# STM32F1xx.net
KiCad netlist of a schematic drawn in Altium Designer
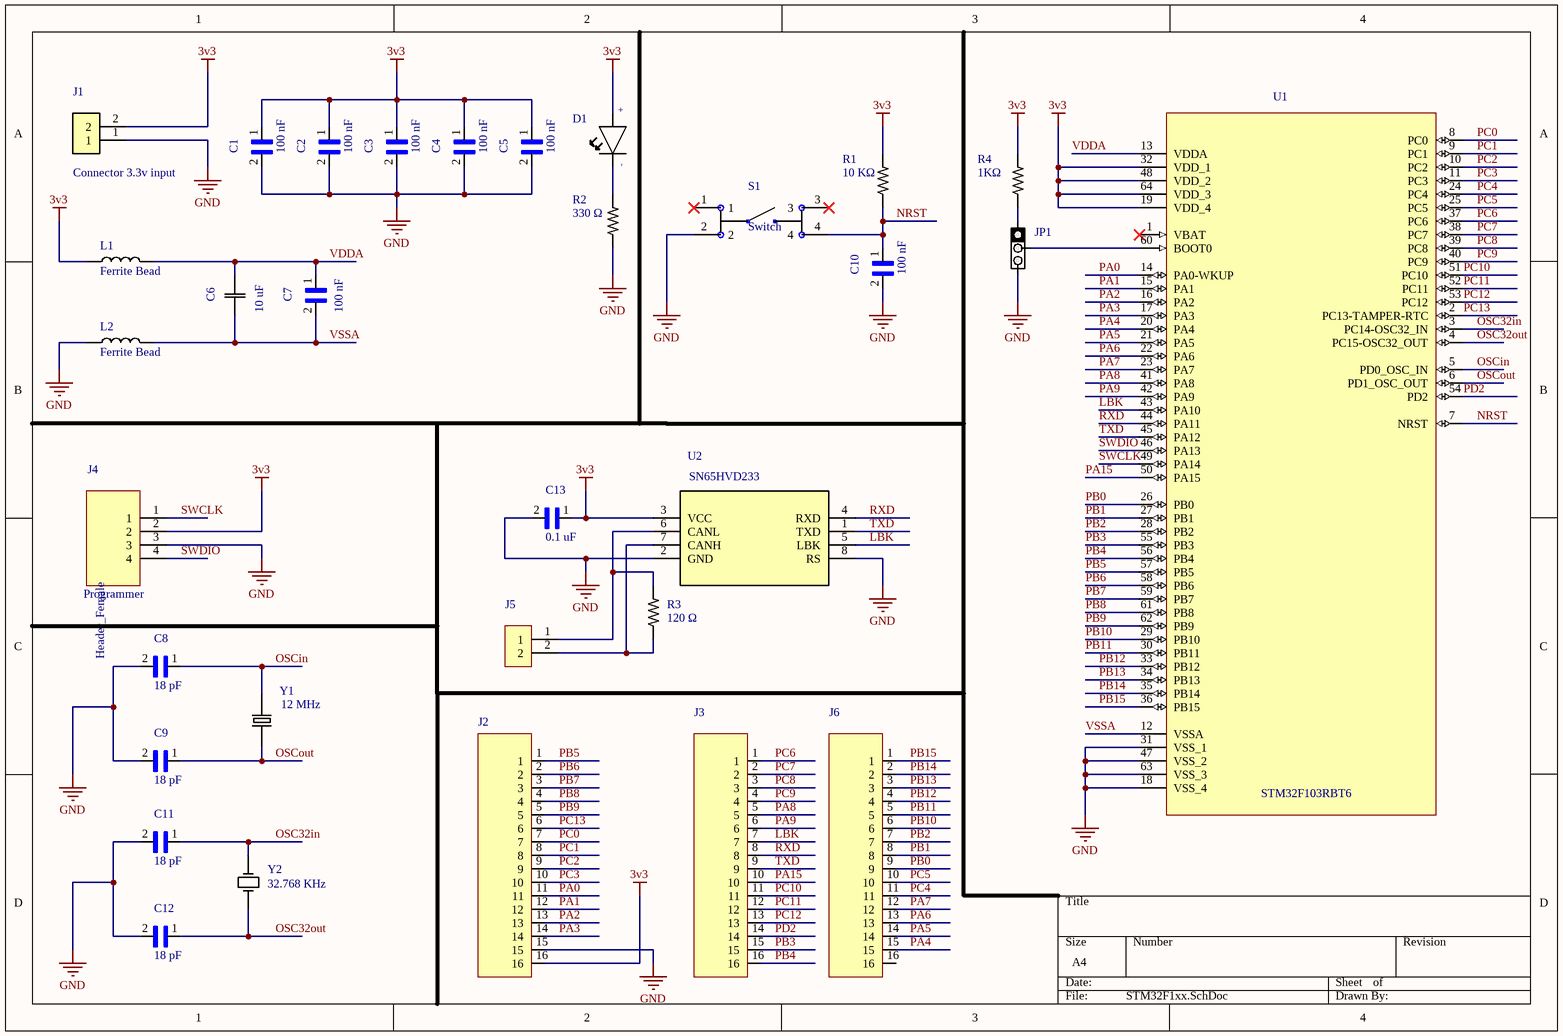
[diagram p0: STM32F1xx.SchDoc]

(export (version "E")
  (design (tool "Eeschema 10.0.6"))
  (components
    (comp (ref "C1")
      (value "100 nF")
      (footprint "*CAPC2012X135N")
      (description "Cap Ceramic 0.1uF 50Vdc X7R 10% SMD 805 125Â°C Embossed T/R")
      (fields (field (name "MF") "Murata Electronics") (field (name "MP") "GCD21BR71H104KA01L"))
      (libsource (lib "Cap_805") (part "GCD21BR71H104KA01L"))
    )
    (comp (ref "C2")
      (value "100 nF")
      (footprint "*CAPC2012X135N")
      (description "Cap Ceramic 0.1uF 50Vdc X7R 10% SMD 805 125Â°C Embossed T/R")
      (fields (field (name "MF") "Murata Electronics") (field (name "MP") "GCD21BR71H104KA01L"))
      (libsource (lib "Cap_805") (part "GCD21BR71H104KA01L"))
    )
    (comp (ref "C3")
      (value "100 nF")
      (footprint "*CAPC2012X135N")
      (description "Cap Ceramic 0.1uF 50Vdc X7R 10% SMD 805 125Â°C Embossed T/R")
      (fields (field (name "MF") "Murata Electronics") (field (name "MP") "GCD21BR71H104KA01L"))
      (libsource (lib "Cap_805") (part "GCD21BR71H104KA01L"))
    )
    (comp (ref "C4")
      (value "100 nF")
      (footprint "*CAPC2012X135N")
      (description "Cap Ceramic 0.1uF 50Vdc X7R 10% SMD 805 125Â°C Embossed T/R")
      (fields (field (name "MF") "Murata Electronics") (field (name "MP") "GCD21BR71H104KA01L"))
      (libsource (lib "Cap_805") (part "GCD21BR71H104KA01L"))
    )
    (comp (ref "C5")
      (value "100 nF")
      (footprint "*CAPC2012X135N")
      (description "Cap Ceramic 0.1uF 50Vdc X7R 10% SMD 805 125Â°C Embossed T/R")
      (fields (field (name "MF") "Murata Electronics") (field (name "MP") "GCD21BR71H104KA01L"))
      (libsource (lib "Cap_805") (part "GCD21BR71H104KA01L"))
    )
    (comp (ref "C6")
      (value "10 uF")
      (footprint "CAPC3216X94N")
      (description "1206 100 nF 16 V Â±10 % Tolerance X7R SMT Multilayer Ceramic Capacitor")
      (fields (field (name "MP") "1206YC104KAT2A") (field (name "MF") "AVX"))
      (libsource (lib "Cap_1206") (part "1206YC104KAT2A"))
    )
    (comp (ref "C7")
      (value "100 nF")
      (footprint "*CAPC2012X135N")
      (description "Cap Ceramic 0.1uF 50Vdc X7R 10% SMD 805 125Â°C Embossed T/R")
      (fields (field (name "MF") "Murata Electronics") (field (name "MP") "GCD21BR71H104KA01L"))
      (libsource (lib "Cap_805") (part "GCD21BR71H104KA01L"))
    )
    (comp (ref "C8")
      (value "18 pF")
      (footprint "*CAPC2012X135N")
      (description "Cap Ceramic 0.1uF 50Vdc X7R 10% SMD 805 125Â°C Embossed T/R")
      (fields (field (name "MF") "Murata Electronics") (field (name "MP") "GCD21BR71H104KA01L"))
      (libsource (lib "Cap_805") (part "GCD21BR71H104KA01L"))
    )
    (comp (ref "C9")
      (value "18 pF")
      (footprint "*CAPC2012X135N")
      (description "Cap Ceramic 0.1uF 50Vdc X7R 10% SMD 805 125Â°C Embossed T/R")
      (fields (field (name "MF") "Murata Electronics") (field (name "MP") "GCD21BR71H104KA01L"))
      (libsource (lib "Cap_805") (part "GCD21BR71H104KA01L"))
    )
    (comp (ref "C10")
      (value "100 nF")
      (footprint "*CAPC2012X135N")
      (description "Cap Ceramic 0.1uF 50Vdc X7R 10% SMD 805 125Â°C Embossed T/R")
      (fields (field (name "MF") "Murata Electronics") (field (name "MP") "GCD21BR71H104KA01L"))
      (libsource (lib "Cap_805") (part "GCD21BR71H104KA01L"))
    )
    (comp (ref "C11")
      (value "18 pF")
      (footprint "*CAPC2012X135N")
      (description "Cap Ceramic 0.1uF 50Vdc X7R 10% SMD 805 125Â°C Embossed T/R")
      (fields (field (name "MF") "Murata Electronics") (field (name "MP") "GCD21BR71H104KA01L"))
      (libsource (lib "Cap_805") (part "GCD21BR71H104KA01L"))
    )
    (comp (ref "C12")
      (value "18 pF")
      (footprint "*CAPC2012X135N")
      (description "Cap Ceramic 0.1uF 50Vdc X7R 10% SMD 805 125Â°C Embossed T/R")
      (fields (field (name "MF") "Murata Electronics") (field (name "MP") "GCD21BR71H104KA01L"))
      (libsource (lib "Cap_805") (part "GCD21BR71H104KA01L"))
    )
    (comp (ref "C13")
      (value "0.1 uF")
      (footprint "*CAPC2012X135N")
      (description "Cap Ceramic 0.1uF 50Vdc X7R 10% SMD 805 125Â°C Embossed T/R")
      (fields (field (name "MF") "Murata Electronics") (field (name "MP") "GCD21BR71H104KA01L"))
      (libsource (lib "Cap_805") (part "GCD21BR71H104KA01L"))
    )
    (comp (ref "D1")
      (value "LED1206")
      (footprint "WL-SMCW_0603")
      (description "LED, 1206, AMBER, 140MCD, 605NM; Bulb Size: -; LED Colour: Ambre; Luminous Intensi")
      (fields (field (name "MF") "Wurth Electronics") (field (name "DIGI-KEY_PART_NUMBER") "732-4988-1-ND"))
      (libsource (lib "LED_0805") (part "WL-SMCW"))
    )
    (comp (ref "J1")
      (value "Connector 3.3v input")
      (footprint "*MOLEX_0022272031")
      (fields
        (field (name "DIGI-KEY_PART_NUMBER") "WM4112-ND")
        (field (name "MF") "Molex")
        (field (name "MP") "0022272031")
      )
      (libsource (lib "Connector_2Pins") (part "0022272031"))
    )
    (comp (ref "J2")
      (value "Pin Header")
      (footprint "*TE_9-146281-0")
      (description "20 MODII HDR SRST")
      (fields (field (name "CREATED BY") "Alireza Nami"))
      (libsource (lib "Header_F_16") (part "Pin Header"))
    )
    (comp (ref "J3")
      (value "Pin Header")
      (footprint "*TE_9-146281-0")
      (description "20 MODII HDR SRST")
      (fields (field (name "CREATED BY") "Alireza Nami"))
      (libsource (lib "Header_F_16") (part "Pin Header"))
    )
    (comp (ref "J4")
      (value "Programmer")
      (footprint "TE_7-534206-0")
      (description "40 MODII VRT DR CE 100/115")
      (fields (field (name "MP") "7-534206-0") (field (name "MF") "TE Connectivity"))
      (libsource (lib "Header_F_4") (part "7-534206-0"))
    )
    (comp (ref "J5")
      (value "Terminal")
      (footprint "TE_1776266-4")
      (description "Conn Terminal Block 2 POS 5mm Screw")
      (fields (field (name "MP") "1776266-4") (field (name "MF") "TE Connectivity"))
      (libsource (lib "Terminal_2P") (part "Terminal"))
    )
    (comp (ref "J6")
      (value "Pin Header")
      (footprint "*TE_9-146281-0")
      (description "20 MODII HDR SRST")
      (fields (field (name "CREATED BY") "Alireza Nami"))
      (libsource (lib "Header_F_16") (part "Pin Header"))
    )
    (comp (ref "JP1")
      (value "JMPR3")
      (footprint "JMPR3")
      (fields
        (field (name "MANUFACTURER") "Sullins Connector Solutions")
        (field (name "MANUFACTURER PART NUMBER") "PBC36SAAN")
      )
      (libsource (lib "vh_altium_library") (part "JMPR3"))
    )
    (comp (ref "L1")
      (value "Ferrite Bead")
      (footprint "*RESC3216X70")
      (fields (field (name "MF") "Panasonic") (field (name "MP") "EXCML32A680U"))
      (libsource (lib "Ferrite_Bead_1206") (part "Ferrite Bead"))
    )
    (comp (ref "L2")
      (value "Ferrite Bead")
      (footprint "*RESC3216X70")
      (fields (field (name "MF") "Panasonic") (field (name "MP") "EXCML32A680U"))
      (libsource (lib "Ferrite_Bead_1206") (part "Ferrite Bead"))
    )
    (comp (ref "R1")
      (value "10 KΩ")
      (footprint "*RESC2012X65N")
      (description "Res Thick Film 0805 118 Ohm 1% 1/3W Â±100ppm/Â°C Molded SMD SMD T/R")
      (fields (field (name "MP") "CRGH0805F118R") (field (name "MF") "TE Connectivity"))
      (libsource (lib "Res_805") (part "CRGH0805F118R"))
    )
    (comp (ref "R2")
      (value "330 Ω")
      (footprint "*RESC2012X65N")
      (description "Res Thick Film 0805 118 Ohm 1% 1/3W Â±100ppm/Â°C Molded SMD SMD T/R")
      (fields (field (name "MP") "CRGH0805F118R") (field (name "MF") "TE Connectivity"))
      (libsource (lib "Res_805") (part "CRGH0805F118R"))
    )
    (comp (ref "R3")
      (value "120 Ω")
      (footprint "*RESC2012X65N")
      (description "Res Thick Film 0805 118 Ohm 1% 1/3W Â±100ppm/Â°C Molded SMD SMD T/R")
      (fields (field (name "MP") "CRGH0805F118R") (field (name "MF") "TE Connectivity"))
      (libsource (lib "Res_805") (part "CRGH0805F118R"))
    )
    (comp (ref "R4")
      (value "1KΩ")
      (footprint "*RESC2012X65N")
      (description "Res Thick Film 0805 118 Ohm 1% 1/3W Â±100ppm/Â°C Molded SMD SMD T/R")
      (fields (field (name "MP") "CRGH0805F118R") (field (name "MF") "TE Connectivity"))
      (libsource (lib "Res_805") (part "CRGH0805F118R"))
    )
    (comp (ref "S1")
      (value "Switch")
      (footprint "SW_FSM4JSMAATR")
      (description "spst, Tactile / Jog, Industrial Control, Switches, switch, white, smd, tactile")
      (fields (field (name "MF") "Alco") (field (name "MP") "FSM4JSMAATR"))
      (libsource (lib "TactileSwitch_SMD") (part "FSM4JSMAATR"))
    )
    (comp (ref "U1")
      (value "STM32F103RBT6")
      (footprint "QFP50P1200X1200X160-64N")
      (fields (field (name "DIGI-KEY_PART_NUMBER") "497-6066-ND") (field (name "MF") "STMicroelectronics"))
      (libsource (lib "STM32F103RBT6") (part "STM32F103RBT6"))
    )
    (comp (ref "U2")
      (value "SN65HVD233")
      (footprint "*SOIC8")
      (description "Enhanced Product 3.3-V CAN Tranceiver 8-SOIC -55 to 125")
      (fields (field (name "MP") "SN65HVD233MDREP") (field (name "DIGI-KEY_PART_NUMBER") "296-23973-1-ND"))
      (libsource (lib "SN65HVD233") (part "SN65HVD233MDREP"))
    )
    (comp (ref "Y1")
      (value "12 MHz")
      (footprint "XTAL_ECS-80-18-4X")
      (description "HC-49USX Series 8 MHz Â±30 ppm 18 pF -10 to +70 Â°C Through Hole Crystal - HC-49/U")
      (fields (field (name "MP") "ECS-80-18-4X") (field (name "DIGI-KEY_PART_NUMBER") "X1093-ND"))
      (libsource (lib "Crystal_DIP") (part "ECS-80-18-4X"))
    )
    (comp (ref "Y2")
      (value "32.768 KHz")
      (footprint "*XTAL_AB38T-32.768KHZ")
      (description "AB38T Series 32.768 kHz Â±20 ppm 12.5 pF -10 to +60 Â°C Tuning Fork Crystal")
      (fields (field (name "MP") "AB38T-32.768KHZ") (field (name "MF") "Abracon"))
      (libsource (lib "Crystal_32KHz_DIP") (part "AB38T-32.768KHZ"))
    )
  )
  (nets
    (net (code "1") (name "/LBK") (class "Default")
      (node (ref "J3") (pin "7") (pinfunction "7_7") (pintype "passive"))
      (node (ref "U1") (pin "43") (pinfunction "PA10_43") (pintype "bidirectional"))
      (node (ref "U2") (pin "5") (pinfunction "LBK_5") (pintype "passive"))
    )
    (net (code "2") (name "/NRST") (class "Default")
      (node (ref "C10") (pin "1") (pinfunction "1_1") (pintype "passive"))
      (node (ref "R1") (pin "1") (pinfunction "1_1") (pintype "passive"))
      (node (ref "S1") (pin "4") (pinfunction "4_4") (pintype "passive"))
      (node (ref "U1") (pin "7") (pinfunction "NRST_7") (pintype "bidirectional"))
    )
    (net (code "3") (name "/OSC32in") (class "Default")
      (node (ref "C11") (pin "1") (pinfunction "1_1") (pintype "passive"))
      (node (ref "U1") (pin "3") (pinfunction "PC14-OSC32_IN_3") (pintype "bidirectional"))
      (node (ref "Y2") (pin "1") (pinfunction "1_1") (pintype "passive"))
    )
    (net (code "4") (name "/OSC32out") (class "Default")
      (node (ref "C12") (pin "1") (pinfunction "1_1") (pintype "passive"))
      (node (ref "U1") (pin "4") (pinfunction "PC15-OSC32_OUT_4") (pintype "bidirectional"))
      (node (ref "Y2") (pin "2") (pinfunction "2_2") (pintype "passive"))
    )
    (net (code "5") (name "/OSCin") (class "Default")
      (node (ref "C8") (pin "1") (pinfunction "1_1") (pintype "passive"))
      (node (ref "U1") (pin "5") (pinfunction "PD0_OSC_IN_5") (pintype "bidirectional"))
      (node (ref "Y1") (pin "1") (pinfunction "1_1") (pintype "passive"))
    )
    (net (code "6") (name "/OSCout") (class "Default")
      (node (ref "C9") (pin "1") (pinfunction "1_1") (pintype "passive"))
      (node (ref "U1") (pin "6") (pinfunction "PD1_OSC_OUT_6") (pintype "bidirectional"))
      (node (ref "Y1") (pin "2") (pinfunction "2_2") (pintype "passive"))
    )
    (net (code "7") (name "/PA0") (class "Default")
      (node (ref "J2") (pin "11") (pinfunction "11_11") (pintype "passive"))
      (node (ref "U1") (pin "14") (pinfunction "PA0-WKUP_14") (pintype "bidirectional"))
    )
    (net (code "8") (name "/PA1") (class "Default")
      (node (ref "J2") (pin "12") (pinfunction "12_12") (pintype "passive"))
      (node (ref "U1") (pin "15") (pinfunction "PA1_15") (pintype "bidirectional"))
    )
    (net (code "9") (name "/PA2") (class "Default")
      (node (ref "J2") (pin "13") (pinfunction "13_13") (pintype "passive"))
      (node (ref "U1") (pin "16") (pinfunction "PA2_16") (pintype "bidirectional"))
    )
    (net (code "10") (name "/PA3") (class "Default")
      (node (ref "J2") (pin "14") (pinfunction "14_14") (pintype "passive"))
      (node (ref "U1") (pin "17") (pinfunction "PA3_17") (pintype "bidirectional"))
    )
    (net (code "11") (name "/PA4") (class "Default")
      (node (ref "J6") (pin "15") (pinfunction "15_15") (pintype "passive"))
      (node (ref "U1") (pin "20") (pinfunction "PA4_20") (pintype "bidirectional"))
    )
    (net (code "12") (name "/PA5") (class "Default")
      (node (ref "J6") (pin "14") (pinfunction "14_14") (pintype "passive"))
      (node (ref "U1") (pin "21") (pinfunction "PA5_21") (pintype "bidirectional"))
    )
    (net (code "13") (name "/PA6") (class "Default")
      (node (ref "J6") (pin "13") (pinfunction "13_13") (pintype "passive"))
      (node (ref "U1") (pin "22") (pinfunction "PA6_22") (pintype "bidirectional"))
    )
    (net (code "14") (name "/PA7") (class "Default")
      (node (ref "J6") (pin "12") (pinfunction "12_12") (pintype "passive"))
      (node (ref "U1") (pin "23") (pinfunction "PA7_23") (pintype "bidirectional"))
    )
    (net (code "15") (name "/PA8") (class "Default")
      (node (ref "J3") (pin "5") (pinfunction "5_5") (pintype "passive"))
      (node (ref "U1") (pin "41") (pinfunction "PA8_41") (pintype "bidirectional"))
    )
    (net (code "16") (name "/PA9") (class "Default")
      (node (ref "J3") (pin "6") (pinfunction "6_6") (pintype "passive"))
      (node (ref "U1") (pin "42") (pinfunction "PA9_42") (pintype "bidirectional"))
    )
    (net (code "17") (name "/PA15") (class "Default")
      (node (ref "J3") (pin "10") (pinfunction "10_10") (pintype "passive"))
      (node (ref "U1") (pin "50") (pinfunction "PA15_50") (pintype "bidirectional"))
    )
    (net (code "18") (name "/PB0") (class "Default")
      (node (ref "J6") (pin "9") (pinfunction "9_9") (pintype "passive"))
      (node (ref "U1") (pin "26") (pinfunction "PB0_26") (pintype "bidirectional"))
    )
    (net (code "19") (name "/PB1") (class "Default")
      (node (ref "J6") (pin "8") (pinfunction "8_8") (pintype "passive"))
      (node (ref "U1") (pin "27") (pinfunction "PB1_27") (pintype "bidirectional"))
    )
    (net (code "20") (name "/PB2") (class "Default")
      (node (ref "J6") (pin "7") (pinfunction "7_7") (pintype "passive"))
      (node (ref "U1") (pin "28") (pinfunction "PB2_28") (pintype "bidirectional"))
    )
    (net (code "21") (name "/PB3") (class "Default")
      (node (ref "J3") (pin "15") (pinfunction "15_15") (pintype "passive"))
      (node (ref "U1") (pin "55") (pinfunction "PB3_55") (pintype "bidirectional"))
    )
    (net (code "22") (name "/PB4") (class "Default")
      (node (ref "J3") (pin "16") (pinfunction "16_16") (pintype "passive"))
      (node (ref "U1") (pin "56") (pinfunction "PB4_56") (pintype "bidirectional"))
    )
    (net (code "23") (name "/PB5") (class "Default")
      (node (ref "J2") (pin "1") (pinfunction "1_1") (pintype "passive"))
      (node (ref "U1") (pin "57") (pinfunction "PB5_57") (pintype "bidirectional"))
    )
    (net (code "24") (name "/PB6") (class "Default")
      (node (ref "J2") (pin "2") (pinfunction "2_2") (pintype "passive"))
      (node (ref "U1") (pin "58") (pinfunction "PB6_58") (pintype "bidirectional"))
    )
    (net (code "25") (name "/PB7") (class "Default")
      (node (ref "J2") (pin "3") (pinfunction "3_3") (pintype "passive"))
      (node (ref "U1") (pin "59") (pinfunction "PB7_59") (pintype "bidirectional"))
    )
    (net (code "26") (name "/PB8") (class "Default")
      (node (ref "J2") (pin "4") (pinfunction "4_4") (pintype "passive"))
      (node (ref "U1") (pin "61") (pinfunction "PB8_61") (pintype "bidirectional"))
    )
    (net (code "27") (name "/PB9") (class "Default")
      (node (ref "J2") (pin "5") (pinfunction "5_5") (pintype "passive"))
      (node (ref "U1") (pin "62") (pinfunction "PB9_62") (pintype "bidirectional"))
    )
    (net (code "28") (name "/PB10") (class "Default")
      (node (ref "J6") (pin "6") (pinfunction "6_6") (pintype "passive"))
      (node (ref "U1") (pin "29") (pinfunction "PB10_29") (pintype "bidirectional"))
    )
    (net (code "29") (name "/PB11") (class "Default")
      (node (ref "J6") (pin "5") (pinfunction "5_5") (pintype "passive"))
      (node (ref "U1") (pin "30") (pinfunction "PB11_30") (pintype "bidirectional"))
    )
    (net (code "30") (name "/PB12") (class "Default")
      (node (ref "J6") (pin "4") (pinfunction "4_4") (pintype "passive"))
      (node (ref "U1") (pin "33") (pinfunction "PB12_33") (pintype "bidirectional"))
    )
    (net (code "31") (name "/PB13") (class "Default")
      (node (ref "J6") (pin "3") (pinfunction "3_3") (pintype "passive"))
      (node (ref "U1") (pin "34") (pinfunction "PB13_34") (pintype "bidirectional"))
    )
    (net (code "32") (name "/PB14") (class "Default")
      (node (ref "J6") (pin "2") (pinfunction "2_2") (pintype "passive"))
      (node (ref "U1") (pin "35") (pinfunction "PB14_35") (pintype "bidirectional"))
    )
    (net (code "33") (name "/PB15") (class "Default")
      (node (ref "J6") (pin "1") (pinfunction "1_1") (pintype "passive"))
      (node (ref "U1") (pin "36") (pinfunction "PB15_36") (pintype "bidirectional"))
    )
    (net (code "34") (name "/PC0") (class "Default")
      (node (ref "J2") (pin "7") (pinfunction "7_7") (pintype "passive"))
      (node (ref "U1") (pin "8") (pinfunction "PC0_8") (pintype "bidirectional"))
    )
    (net (code "35") (name "/PC1") (class "Default")
      (node (ref "J2") (pin "8") (pinfunction "8_8") (pintype "passive"))
      (node (ref "U1") (pin "9") (pinfunction "PC1_9") (pintype "bidirectional"))
    )
    (net (code "36") (name "/PC2") (class "Default")
      (node (ref "J2") (pin "9") (pinfunction "9_9") (pintype "passive"))
      (node (ref "U1") (pin "10") (pinfunction "PC2_10") (pintype "bidirectional"))
    )
    (net (code "37") (name "/PC3") (class "Default")
      (node (ref "J2") (pin "10") (pinfunction "10_10") (pintype "passive"))
      (node (ref "U1") (pin "11") (pinfunction "PC3_11") (pintype "bidirectional"))
    )
    (net (code "38") (name "/PC4") (class "Default")
      (node (ref "J6") (pin "11") (pinfunction "11_11") (pintype "passive"))
      (node (ref "U1") (pin "24") (pinfunction "PC4_24") (pintype "bidirectional"))
    )
    (net (code "39") (name "/PC5") (class "Default")
      (node (ref "J6") (pin "10") (pinfunction "10_10") (pintype "passive"))
      (node (ref "U1") (pin "25") (pinfunction "PC5_25") (pintype "bidirectional"))
    )
    (net (code "40") (name "/PC6") (class "Default")
      (node (ref "J3") (pin "1") (pinfunction "1_1") (pintype "passive"))
      (node (ref "U1") (pin "37") (pinfunction "PC6_37") (pintype "bidirectional"))
    )
    (net (code "41") (name "/PC7") (class "Default")
      (node (ref "J3") (pin "2") (pinfunction "2_2") (pintype "passive"))
      (node (ref "U1") (pin "38") (pinfunction "PC7_38") (pintype "bidirectional"))
    )
    (net (code "42") (name "/PC8") (class "Default")
      (node (ref "J3") (pin "3") (pinfunction "3_3") (pintype "passive"))
      (node (ref "U1") (pin "39") (pinfunction "PC8_39") (pintype "bidirectional"))
    )
    (net (code "43") (name "/PC9") (class "Default")
      (node (ref "J3") (pin "4") (pinfunction "4_4") (pintype "passive"))
      (node (ref "U1") (pin "40") (pinfunction "PC9_40") (pintype "bidirectional"))
    )
    (net (code "44") (name "/PC10") (class "Default")
      (node (ref "J3") (pin "11") (pinfunction "11_11") (pintype "passive"))
      (node (ref "U1") (pin "51") (pinfunction "PC10_51") (pintype "bidirectional"))
    )
    (net (code "45") (name "/PC11") (class "Default")
      (node (ref "J3") (pin "12") (pinfunction "12_12") (pintype "passive"))
      (node (ref "U1") (pin "52") (pinfunction "PC11_52") (pintype "bidirectional"))
    )
    (net (code "46") (name "/PC12") (class "Default")
      (node (ref "J3") (pin "13") (pinfunction "13_13") (pintype "passive"))
      (node (ref "U1") (pin "53") (pinfunction "PC12_53") (pintype "bidirectional"))
    )
    (net (code "47") (name "/PC13") (class "Default")
      (node (ref "J2") (pin "6") (pinfunction "6_6") (pintype "passive"))
      (node (ref "U1") (pin "2") (pinfunction "PC13-TAMPER-RTC_2") (pintype "bidirectional"))
    )
    (net (code "48") (name "/PD2") (class "Default")
      (node (ref "J3") (pin "14") (pinfunction "14_14") (pintype "passive"))
      (node (ref "U1") (pin "54") (pinfunction "PD2_54") (pintype "bidirectional"))
    )
    (net (code "49") (name "/RXD") (class "Default")
      (node (ref "J3") (pin "8") (pinfunction "8_8") (pintype "passive"))
      (node (ref "U1") (pin "44") (pinfunction "PA11_44") (pintype "bidirectional"))
      (node (ref "U2") (pin "4") (pinfunction "RXD_4") (pintype "passive"))
    )
    (net (code "50") (name "/SWCLK") (class "Default")
      (node (ref "J4") (pin "1") (pinfunction "1_1") (pintype "passive"))
      (node (ref "U1") (pin "49") (pinfunction "PA14_49") (pintype "bidirectional"))
    )
    (net (code "51") (name "/SWDIO") (class "Default")
      (node (ref "J4") (pin "4") (pinfunction "4_4") (pintype "passive"))
      (node (ref "U1") (pin "46") (pinfunction "PA13_46") (pintype "bidirectional"))
    )
    (net (code "52") (name "/TXD") (class "Default")
      (node (ref "J3") (pin "9") (pinfunction "9_9") (pintype "passive"))
      (node (ref "U1") (pin "45") (pinfunction "PA12_45") (pintype "bidirectional"))
      (node (ref "U2") (pin "1") (pinfunction "TXD_1") (pintype "passive"))
    )
    (net (code "53") (name "/VDDA") (class "Default")
      (node (ref "C6") (pin "2") (pinfunction "C2_2") (pintype "passive"))
      (node (ref "C7") (pin "1") (pinfunction "1_1") (pintype "passive"))
      (node (ref "L1") (pin "2") (pinfunction "2_2") (pintype "passive"))
      (node (ref "U1") (pin "13") (pinfunction "VDDA_13") (pintype "power_in"))
    )
    (net (code "54") (name "/VSSA") (class "Default")
      (node (ref "C6") (pin "1") (pinfunction "C1_1") (pintype "passive"))
      (node (ref "C7") (pin "2") (pinfunction "2_2") (pintype "passive"))
      (node (ref "L2") (pin "2") (pinfunction "2_2") (pintype "passive"))
      (node (ref "U1") (pin "12") (pinfunction "VSSA_12") (pintype "passive"))
    )
    (net (code "55") (name "3v3") (class "Default")
      (node (ref "C1") (pin "1") (pinfunction "1_1") (pintype "passive"))
      (node (ref "C13") (pin "1") (pinfunction "1_1") (pintype "passive"))
      (node (ref "C2") (pin "1") (pinfunction "1_1") (pintype "passive"))
      (node (ref "C3") (pin "1") (pinfunction "1_1") (pintype "passive"))
      (node (ref "C4") (pin "1") (pinfunction "1_1") (pintype "passive"))
      (node (ref "C5") (pin "1") (pinfunction "1_1") (pintype "passive"))
      (node (ref "D1") (pin "2") (pinfunction "2_2") (pintype "passive"))
      (node (ref "J1") (pin "2") (pinfunction "2_2") (pintype "passive"))
      (node (ref "J2") (pin "16") (pinfunction "16_16") (pintype "passive"))
      (node (ref "J4") (pin "2") (pinfunction "2_2") (pintype "passive"))
      (node (ref "L1") (pin "1") (pinfunction "1_1") (pintype "passive"))
      (node (ref "R1") (pin "2") (pinfunction "2_2") (pintype "passive"))
      (node (ref "R4") (pin "2") (pinfunction "2_2") (pintype "passive"))
      (node (ref "U1") (pin "19") (pinfunction "VDD_4_19") (pintype "power_in"))
      (node (ref "U1") (pin "32") (pinfunction "VDD_1_32") (pintype "power_in"))
      (node (ref "U1") (pin "48") (pinfunction "VDD_2_48") (pintype "power_in"))
      (node (ref "U1") (pin "64") (pinfunction "VDD_3_64") (pintype "power_in"))
      (node (ref "U2") (pin "3") (pinfunction "VCC_3") (pintype "power_in"))
    )
    (net (code "56") (name "GND") (class "Default")
      (node (ref "C1") (pin "2") (pinfunction "2_2") (pintype "passive"))
      (node (ref "C10") (pin "2") (pinfunction "2_2") (pintype "passive"))
      (node (ref "C11") (pin "2") (pinfunction "2_2") (pintype "passive"))
      (node (ref "C12") (pin "2") (pinfunction "2_2") (pintype "passive"))
      (node (ref "C13") (pin "2") (pinfunction "2_2") (pintype "passive"))
      (node (ref "C2") (pin "2") (pinfunction "2_2") (pintype "passive"))
      (node (ref "C3") (pin "2") (pinfunction "2_2") (pintype "passive"))
      (node (ref "C4") (pin "2") (pinfunction "2_2") (pintype "passive"))
      (node (ref "C5") (pin "2") (pinfunction "2_2") (pintype "passive"))
      (node (ref "C8") (pin "2") (pinfunction "2_2") (pintype "passive"))
      (node (ref "C9") (pin "2") (pinfunction "2_2") (pintype "passive"))
      (node (ref "J1") (pin "1") (pinfunction "1_1") (pintype "passive"))
      (node (ref "J2") (pin "15") (pinfunction "15_15") (pintype "passive"))
      (node (ref "J4") (pin "3") (pinfunction "3_3") (pintype "passive"))
      (node (ref "JP1") (pin "3") (pintype "passive"))
      (node (ref "L2") (pin "1") (pinfunction "1_1") (pintype "passive"))
      (node (ref "R2") (pin "1") (pinfunction "1_1") (pintype "passive"))
      (node (ref "S1") (pin "2") (pinfunction "2_2") (pintype "passive"))
      (node (ref "U1") (pin "18") (pinfunction "VSS_4_18") (pintype "passive"))
      (node (ref "U1") (pin "31") (pinfunction "VSS_1_31") (pintype "passive"))
      (node (ref "U1") (pin "47") (pinfunction "VSS_2_47") (pintype "passive"))
      (node (ref "U1") (pin "63") (pinfunction "VSS_3_63") (pintype "passive"))
      (node (ref "U2") (pin "2") (pinfunction "GND_2") (pintype "power_in"))
      (node (ref "U2") (pin "8") (pinfunction "RS_8") (pintype "passive"))
    )
    (net (code "57") (name "Net-(D1-Pad1)") (class "Default")
      (node (ref "D1") (pin "1") (pinfunction "1_1") (pintype "passive"))
      (node (ref "R2") (pin "2") (pinfunction "2_2") (pintype "passive"))
    )
    (net (code "58") (name "Net-(JP1-Pad1)") (class "Default")
      (node (ref "JP1") (pin "1") (pintype "passive"))
      (node (ref "R4") (pin "1") (pinfunction "1_1") (pintype "passive"))
    )
    (net (code "59") (name "Net-(U1-BOOT0)") (class "Default")
      (node (ref "JP1") (pin "2") (pintype "passive"))
      (node (ref "U1") (pin "60") (pinfunction "BOOT0_60") (pintype "input"))
    )
    (net (code "60") (name "Net-(U2-CANH)") (class "Default")
      (node (ref "J5") (pin "2") (pinfunction "2_2") (pintype "passive"))
      (node (ref "R3") (pin "1") (pinfunction "1_1") (pintype "passive"))
      (node (ref "U2") (pin "7") (pinfunction "CANH_7") (pintype "passive"))
    )
    (net (code "61") (name "Net-(U2-CANL)") (class "Default")
      (node (ref "J5") (pin "1") (pinfunction "1_1") (pintype "passive"))
      (node (ref "R3") (pin "2") (pinfunction "2_2") (pintype "passive"))
      (node (ref "U2") (pin "6") (pinfunction "CANL_6") (pintype "passive"))
    )
    (net (code "62") (name "unconnected-(J6-Pad16)") (class "Default")
      (node (ref "J6") (pin "16") (pinfunction "16_16") (pintype "passive"))
    )
    (net (code "63") (name "unconnected-(S1-Pad1)") (class "Default")
      (node (ref "S1") (pin "1") (pinfunction "1_1") (pintype "passive+no_connect"))
    )
    (net (code "64") (name "unconnected-(S1-Pad3)") (class "Default")
      (node (ref "S1") (pin "3") (pinfunction "3_3") (pintype "passive+no_connect"))
    )
    (net (code "65") (name "unconnected-(U1-VBAT-Pad1)") (class "Default")
      (node (ref "U1") (pin "1") (pinfunction "VBAT_1") (pintype "input+no_connect"))
    )
  )
)
